# UCD3138_Digital_Controller.net
KiCad netlist of a schematic drawn in Altium Designer
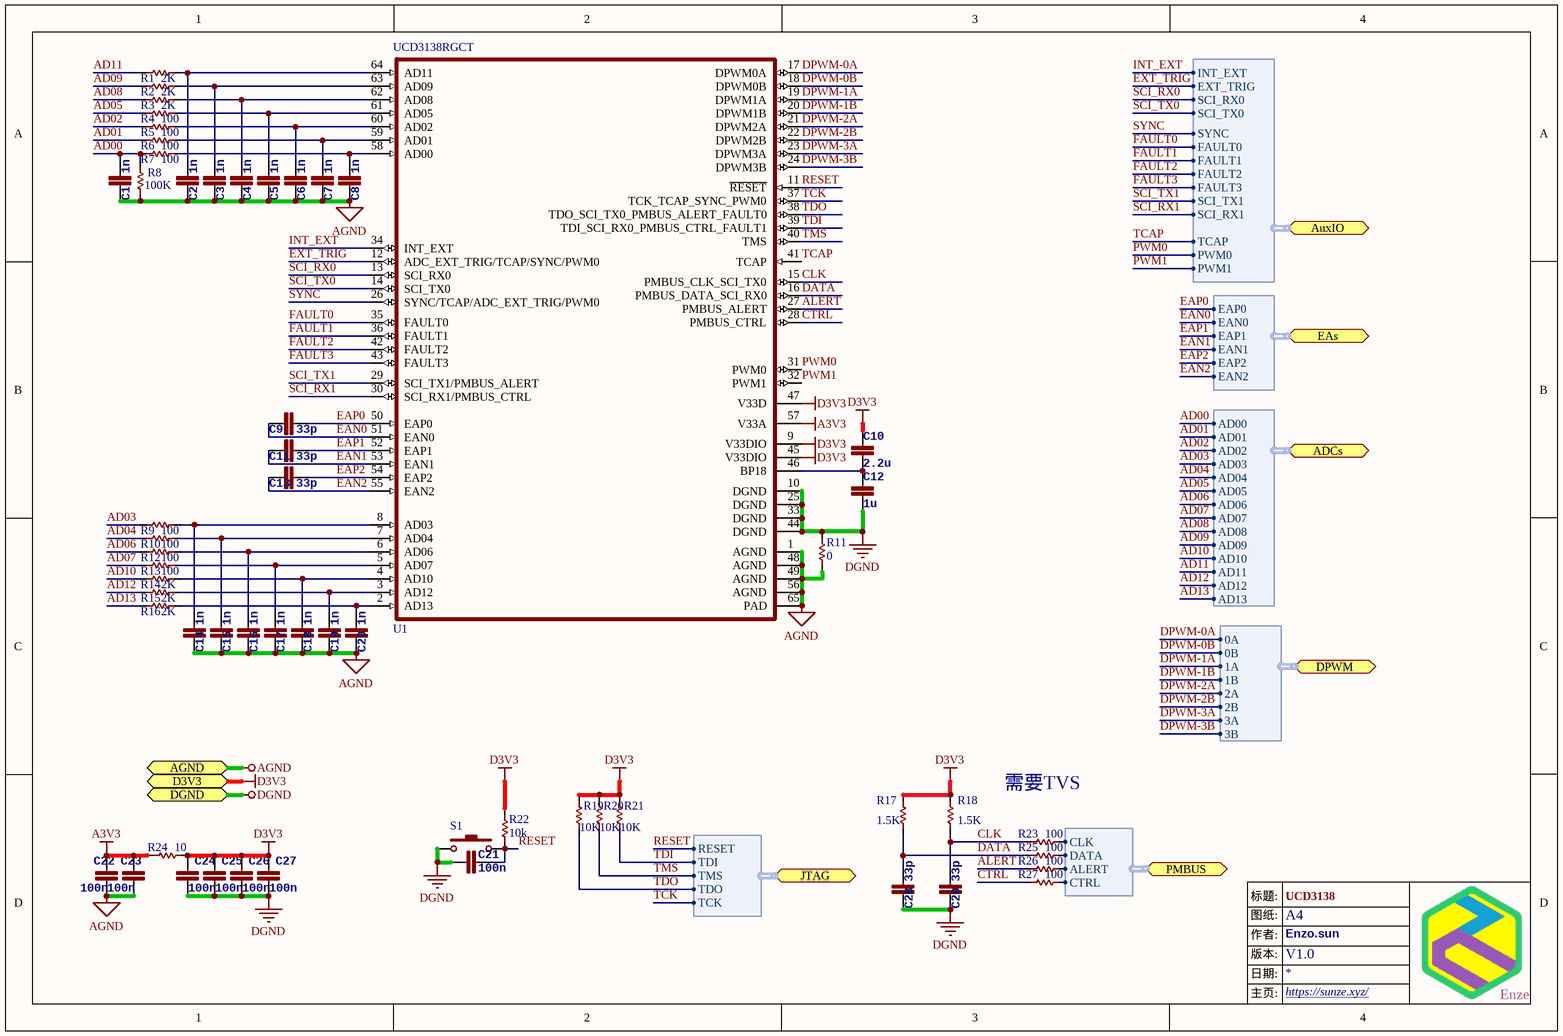
[diagram p0: UCD3138 Digital Controller.SchDoc]

(export (version "E")
  (design (tool "Eeschema 10.0.6"))
  (components
    (comp (ref "C1")
      (value "1n")
      (footprint "0603-R/C-YG")
      (description "<B>CAPACITOR</B>, European symbol")
      (libsource (lib "My_Lib") (part "Capacitor-M"))
    )
    (comp (ref "C2")
      (value "1n")
      (footprint "0603-R/C-YG")
      (description "<B>CAPACITOR</B>, European symbol")
      (libsource (lib "My_Lib") (part "Capacitor-M"))
    )
    (comp (ref "C3")
      (value "1n")
      (footprint "0603-R/C-YG")
      (description "<B>CAPACITOR</B>, European symbol")
      (libsource (lib "My_Lib") (part "Capacitor-M"))
    )
    (comp (ref "C4")
      (value "1n")
      (footprint "0603-R/C-YG")
      (description "<B>CAPACITOR</B>, European symbol")
      (libsource (lib "My_Lib") (part "Capacitor-M"))
    )
    (comp (ref "C5")
      (value "1n")
      (footprint "0603-R/C-YG")
      (description "<B>CAPACITOR</B>, European symbol")
      (libsource (lib "My_Lib") (part "Capacitor-M"))
    )
    (comp (ref "C6")
      (value "1n")
      (footprint "0603-R/C-YG")
      (description "<B>CAPACITOR</B>, European symbol")
      (libsource (lib "My_Lib") (part "Capacitor-M"))
    )
    (comp (ref "C7")
      (value "1n")
      (footprint "0603-R/C-YG")
      (description "<B>CAPACITOR</B>, European symbol")
      (libsource (lib "My_Lib") (part "Capacitor-M"))
    )
    (comp (ref "C8")
      (value "1n")
      (footprint "0603-R/C-YG")
      (description "<B>CAPACITOR</B>, European symbol")
      (libsource (lib "My_Lib") (part "Capacitor-M"))
    )
    (comp (ref "C9")
      (value "33p")
      (footprint "0603-R/C-YG")
      (description "<B>CAPACITOR</B>, European symbol")
      (libsource (lib "") (part "Capacitor-M_1"))
    )
    (comp (ref "C10")
      (value "2.2u")
      (footprint "0603-R/C-YG")
      (description "<B>CAPACITOR</B>, European symbol")
      (libsource (lib "My_Lib") (part "Capacitor-M"))
    )
    (comp (ref "C11")
      (value "33p")
      (footprint "0603-R/C-YG")
      (description "<B>CAPACITOR</B>, European symbol")
      (libsource (lib "") (part "Capacitor-M_1"))
    )
    (comp (ref "C12")
      (value "1u")
      (footprint "0603-R/C-YG")
      (description "<B>CAPACITOR</B>, European symbol")
      (libsource (lib "My_Lib") (part "Capacitor-M"))
    )
    (comp (ref "C13")
      (value "33p")
      (footprint "0603-R/C-YG")
      (description "<B>CAPACITOR</B>, European symbol")
      (libsource (lib "") (part "Capacitor-M_1"))
    )
    (comp (ref "C14")
      (value "1n")
      (footprint "0603-R/C-YG")
      (description "<B>CAPACITOR</B>, European symbol")
      (libsource (lib "My_Lib") (part "Capacitor-M"))
    )
    (comp (ref "C15")
      (value "1n")
      (footprint "0603-R/C-YG")
      (description "<B>CAPACITOR</B>, European symbol")
      (libsource (lib "My_Lib") (part "Capacitor-M"))
    )
    (comp (ref "C16")
      (value "1n")
      (footprint "0603-R/C-YG")
      (description "<B>CAPACITOR</B>, European symbol")
      (libsource (lib "My_Lib") (part "Capacitor-M"))
    )
    (comp (ref "C17")
      (value "1n")
      (footprint "0603-R/C-YG")
      (description "<B>CAPACITOR</B>, European symbol")
      (libsource (lib "My_Lib") (part "Capacitor-M"))
    )
    (comp (ref "C18")
      (value "1n")
      (footprint "0603-R/C-YG")
      (description "<B>CAPACITOR</B>, European symbol")
      (libsource (lib "My_Lib") (part "Capacitor-M"))
    )
    (comp (ref "C19")
      (value "1n")
      (footprint "0603-R/C-YG")
      (description "<B>CAPACITOR</B>, European symbol")
      (libsource (lib "My_Lib") (part "Capacitor-M"))
    )
    (comp (ref "C20")
      (value "1n")
      (footprint "0603-R/C-YG")
      (description "<B>CAPACITOR</B>, European symbol")
      (libsource (lib "My_Lib") (part "Capacitor-M"))
    )
    (comp (ref "C21")
      (value "100n")
      (footprint "0603-R/C-YG")
      (description "<B>CAPACITOR</B>, European symbol")
      (libsource (lib "") (part "Capacitor-M_1"))
    )
    (comp (ref "C22")
      (value "100n")
      (footprint "0603-R/C-YG")
      (description "<B>CAPACITOR</B>, European symbol")
      (libsource (lib "My_Lib") (part "Capacitor-M"))
    )
    (comp (ref "C23")
      (value "100n")
      (footprint "0603-R/C-YG")
      (description "<B>CAPACITOR</B>, European symbol")
      (libsource (lib "My_Lib") (part "Capacitor-M"))
    )
    (comp (ref "C24")
      (value "100n")
      (footprint "0603-R/C-YG")
      (description "<B>CAPACITOR</B>, European symbol")
      (libsource (lib "My_Lib") (part "Capacitor-M"))
    )
    (comp (ref "C25")
      (value "100n")
      (footprint "0603-R/C-YG")
      (description "<B>CAPACITOR</B>, European symbol")
      (libsource (lib "My_Lib") (part "Capacitor-M"))
    )
    (comp (ref "C26")
      (value "100n")
      (footprint "0603-R/C-YG")
      (description "<B>CAPACITOR</B>, European symbol")
      (libsource (lib "My_Lib") (part "Capacitor-M"))
    )
    (comp (ref "C27")
      (value "100n")
      (footprint "0603-R/C-YG")
      (description "<B>CAPACITOR</B>, European symbol")
      (libsource (lib "My_Lib") (part "Capacitor-M"))
    )
    (comp (ref "C28")
      (value "33p")
      (footprint "0603-R/C-YG")
      (description "<B>CAPACITOR</B>, European symbol")
      (libsource (lib "My_Lib") (part "Capacitor-M"))
    )
    (comp (ref "C29")
      (value "33p")
      (footprint "0603-R/C-YG")
      (description "<B>CAPACITOR</B>, European symbol")
      (libsource (lib "My_Lib") (part "Capacitor-M"))
    )
    (comp (ref "R1")
      (value "2K")
      (footprint "0603-R-B")
      (description "电阻")
      (fields (field (name "PUBLISHER") "Altium Limited"))
      (libsource (lib "My_Lib") (part "Resistor-E"))
    )
    (comp (ref "R2")
      (value "2K")
      (footprint "0603-R-B")
      (description "电阻")
      (fields (field (name "PUBLISHER") "Altium Limited"))
      (libsource (lib "My_Lib") (part "Resistor-E"))
    )
    (comp (ref "R3")
      (value "2K")
      (footprint "0603-R-B")
      (description "电阻")
      (fields (field (name "PUBLISHER") "Altium Limited"))
      (libsource (lib "My_Lib") (part "Resistor-E"))
    )
    (comp (ref "R4")
      (value "100")
      (footprint "0603-R-B")
      (description "电阻")
      (fields (field (name "PUBLISHER") "Altium Limited"))
      (libsource (lib "My_Lib") (part "Resistor-E"))
    )
    (comp (ref "R5")
      (value "100")
      (footprint "0603-R-B")
      (description "电阻")
      (fields (field (name "PUBLISHER") "Altium Limited"))
      (libsource (lib "My_Lib") (part "Resistor-E"))
    )
    (comp (ref "R6")
      (value "100")
      (footprint "0603-R-B")
      (description "电阻")
      (fields (field (name "PUBLISHER") "Altium Limited"))
      (libsource (lib "My_Lib") (part "Resistor-E"))
    )
    (comp (ref "R7")
      (value "100")
      (footprint "0603-R-B")
      (description "电阻")
      (fields (field (name "PUBLISHER") "Altium Limited"))
      (libsource (lib "My_Lib") (part "Resistor-E"))
    )
    (comp (ref "R8")
      (value "100K")
      (footprint "0603-R-B")
      (description "电阻")
      (fields (field (name "PUBLISHER") "Altium Limited"))
      (libsource (lib "My_Lib") (part "Resistor-E"))
    )
    (comp (ref "R9")
      (value "100")
      (footprint "0603-R-B")
      (description "电阻")
      (fields (field (name "PUBLISHER") "Altium Limited"))
      (libsource (lib "My_Lib") (part "Resistor-E"))
    )
    (comp (ref "R10")
      (value "100")
      (footprint "0603-R-B")
      (description "电阻")
      (fields (field (name "PUBLISHER") "Altium Limited"))
      (libsource (lib "My_Lib") (part "Resistor-E"))
    )
    (comp (ref "R11")
      (value "0")
      (footprint "0805R")
      (description "电阻")
      (fields (field (name "PUBLISHER") "Altium Limited"))
      (libsource (lib "My_Lib") (part "Resistor-E"))
    )
    (comp (ref "R12")
      (value "100")
      (footprint "0603-R-B")
      (description "电阻")
      (fields (field (name "PUBLISHER") "Altium Limited"))
      (libsource (lib "My_Lib") (part "Resistor-E"))
    )
    (comp (ref "R13")
      (value "100")
      (footprint "0603-R-B")
      (description "电阻")
      (fields (field (name "PUBLISHER") "Altium Limited"))
      (libsource (lib "My_Lib") (part "Resistor-E"))
    )
    (comp (ref "R14")
      (value "2K")
      (footprint "0603-R-B")
      (description "电阻")
      (fields (field (name "PUBLISHER") "Altium Limited"))
      (libsource (lib "My_Lib") (part "Resistor-E"))
    )
    (comp (ref "R15")
      (value "2K")
      (footprint "0603-R-B")
      (description "电阻")
      (fields (field (name "PUBLISHER") "Altium Limited"))
      (libsource (lib "My_Lib") (part "Resistor-E"))
    )
    (comp (ref "R16")
      (value "2K")
      (footprint "0603-R-B")
      (description "电阻")
      (fields (field (name "PUBLISHER") "Altium Limited"))
      (libsource (lib "My_Lib") (part "Resistor-E"))
    )
    (comp (ref "R17")
      (value "1.5K")
      (footprint "0603-R-B")
      (description "电阻")
      (fields (field (name "PUBLISHER") "Altium Limited"))
      (libsource (lib "My_Lib") (part "Resistor-E"))
    )
    (comp (ref "R18")
      (value "1.5K")
      (footprint "0603-R-B")
      (description "电阻")
      (fields (field (name "PUBLISHER") "Altium Limited"))
      (libsource (lib "My_Lib") (part "Resistor-E"))
    )
    (comp (ref "R19")
      (value "10K")
      (footprint "0603-R-B")
      (description "电阻")
      (fields (field (name "PUBLISHER") "Altium Limited"))
      (libsource (lib "My_Lib") (part "Resistor-E"))
    )
    (comp (ref "R20")
      (value "10K")
      (footprint "0603-R-B")
      (description "电阻")
      (fields (field (name "PUBLISHER") "Altium Limited"))
      (libsource (lib "My_Lib") (part "Resistor-E"))
    )
    (comp (ref "R21")
      (value "10K")
      (footprint "0603-R-B")
      (description "电阻")
      (fields (field (name "PUBLISHER") "Altium Limited"))
      (libsource (lib "My_Lib") (part "Resistor-E"))
    )
    (comp (ref "R22")
      (value "10k")
      (footprint "0603-R-B")
      (description "电阻")
      (fields (field (name "PUBLISHER") "Altium Limited"))
      (libsource (lib "My_Lib") (part "Resistor-E"))
    )
    (comp (ref "R23")
      (value "100")
      (footprint "0603-R-B")
      (description "电阻")
      (fields (field (name "PUBLISHER") "Altium Limited"))
      (libsource (lib "My_Lib") (part "Resistor-E"))
    )
    (comp (ref "R24")
      (value "10")
      (footprint "0805R")
      (description "电阻")
      (fields (field (name "PUBLISHER") "Altium Limited"))
      (libsource (lib "My_Lib") (part "Resistor-E"))
    )
    (comp (ref "R25")
      (value "100")
      (footprint "0603-R-B")
      (description "电阻")
      (fields (field (name "PUBLISHER") "Altium Limited"))
      (libsource (lib "My_Lib") (part "Resistor-E"))
    )
    (comp (ref "R26")
      (value "100")
      (footprint "0603-R-B")
      (description "电阻")
      (fields (field (name "PUBLISHER") "Altium Limited"))
      (libsource (lib "My_Lib") (part "Resistor-E"))
    )
    (comp (ref "R27")
      (value "100")
      (footprint "0603-R-B")
      (description "电阻")
      (fields (field (name "PUBLISHER") "Altium Limited"))
      (libsource (lib "My_Lib") (part "Resistor-E"))
    )
    (comp (ref "S1")
      (value "SW-PB")
      (footprint "SW-SMD1")
      (description "Switch")
      (fields (field (name "PUBLISHER") "Altium Limited"))
      (libsource (lib "My_Lib") (part "SW-PB"))
    )
    (comp (ref "UCD3138RGCT")
      (value "U1")
      (footprint "VQFN-64")
      (description "64Pins")
      (libsource (lib "My_Lib") (part "UCD3138RGCT"))
    )
  )
  (nets
    (net (code "7") (name "/AD00") (class "Default")
      (node (ref "C1") (pin "2") (pinfunction "2_2") (pintype "passive"))
      (node (ref "R7") (pin "2") (pinfunction "2_2") (pintype "passive"))
      (node (ref "R8") (pin "1") (pinfunction "1_1") (pintype "passive"))
    )
    (net (code "8") (name "/AD01") (class "Default")
      (node (ref "R6") (pin "2") (pinfunction "2_2") (pintype "passive"))
    )
    (net (code "9") (name "/AD02") (class "Default")
      (node (ref "R5") (pin "2") (pinfunction "2_2") (pintype "passive"))
    )
    (net (code "10") (name "/AD03") (class "Default")
      (node (ref "R9") (pin "2") (pinfunction "2_2") (pintype "passive"))
    )
    (net (code "11") (name "/AD04") (class "Default")
      (node (ref "R10") (pin "2") (pinfunction "2_2") (pintype "passive"))
    )
    (net (code "12") (name "/AD05") (class "Default")
      (node (ref "R4") (pin "2") (pinfunction "2_2") (pintype "passive"))
    )
    (net (code "13") (name "/AD06") (class "Default")
      (node (ref "R12") (pin "2") (pinfunction "2_2") (pintype "passive"))
    )
    (net (code "14") (name "/AD07") (class "Default")
      (node (ref "R13") (pin "2") (pinfunction "2_2") (pintype "passive"))
    )
    (net (code "15") (name "/AD08") (class "Default")
      (node (ref "R3") (pin "2") (pinfunction "2_2") (pintype "passive"))
    )
    (net (code "16") (name "/AD09") (class "Default")
      (node (ref "R2") (pin "2") (pinfunction "2_2") (pintype "passive"))
    )
    (net (code "17") (name "/AD10") (class "Default")
      (node (ref "R14") (pin "2") (pinfunction "2_2") (pintype "passive"))
    )
    (net (code "18") (name "/AD11") (class "Default")
      (node (ref "R1") (pin "2") (pinfunction "2_2") (pintype "passive"))
    )
    (net (code "19") (name "/AD12") (class "Default")
      (node (ref "R15") (pin "2") (pinfunction "2_2") (pintype "passive"))
    )
    (net (code "20") (name "/AD13") (class "Default")
      (node (ref "R16") (pin "2") (pinfunction "2_2") (pintype "passive"))
    )
    (net (code "21") (name "/ALERT") (class "Default")
      (node (ref "R26") (pin "2") (pinfunction "2_2") (pintype "passive"))
      (node (ref "UCD3138RGCT") (pin "27") (pinfunction "PMBUS_ALERT_27") (pintype "bidirectional"))
    )
    (net (code "22") (name "/CLK") (class "Default")
      (node (ref "C29") (pin "2") (pinfunction "2_2") (pintype "passive"))
      (node (ref "R18") (pin "1") (pinfunction "1_1") (pintype "passive"))
      (node (ref "R23") (pin "2") (pinfunction "2_2") (pintype "passive"))
      (node (ref "UCD3138RGCT") (pin "15") (pinfunction "PMBUS_CLK_SCI_TX0_15") (pintype "bidirectional"))
    )
    (net (code "23") (name "/CTRL") (class "Default")
      (node (ref "R27") (pin "2") (pinfunction "2_2") (pintype "passive"))
      (node (ref "UCD3138RGCT") (pin "28") (pinfunction "PMBUS_CTRL_28") (pintype "bidirectional"))
    )
    (net (code "24") (name "/DATA") (class "Default")
      (node (ref "C28") (pin "2") (pinfunction "2_2") (pintype "passive"))
      (node (ref "R17") (pin "1") (pinfunction "1_1") (pintype "passive"))
      (node (ref "R25") (pin "2") (pinfunction "2_2") (pintype "passive"))
      (node (ref "UCD3138RGCT") (pin "16") (pinfunction "PMBUS_DATA_SCI_RX0_16") (pintype "bidirectional"))
    )
    (net (code "25") (name "/DPWM-0A") (class "Default")
      (node (ref "UCD3138RGCT") (pin "17") (pinfunction "DPWM0A_17") (pintype "bidirectional"))
    )
    (net (code "26") (name "/DPWM-0B") (class "Default")
      (node (ref "UCD3138RGCT") (pin "18") (pinfunction "DPWM0B_18") (pintype "bidirectional"))
    )
    (net (code "27") (name "/DPWM-1A") (class "Default")
      (node (ref "UCD3138RGCT") (pin "19") (pinfunction "DPWM1A_19") (pintype "bidirectional"))
    )
    (net (code "28") (name "/DPWM-1B") (class "Default")
      (node (ref "UCD3138RGCT") (pin "20") (pinfunction "DPWM1B_20") (pintype "bidirectional"))
    )
    (net (code "29") (name "/DPWM-2A") (class "Default")
      (node (ref "UCD3138RGCT") (pin "21") (pinfunction "DPWM2A_21") (pintype "bidirectional"))
    )
    (net (code "30") (name "/DPWM-2B") (class "Default")
      (node (ref "UCD3138RGCT") (pin "22") (pinfunction "DPWM2B_22") (pintype "bidirectional"))
    )
    (net (code "31") (name "/DPWM-3A") (class "Default")
      (node (ref "UCD3138RGCT") (pin "23") (pinfunction "DPWM3A_23") (pintype "bidirectional"))
    )
    (net (code "32") (name "/DPWM-3B") (class "Default")
      (node (ref "UCD3138RGCT") (pin "24") (pinfunction "DPWM3B_24") (pintype "bidirectional"))
    )
    (net (code "33") (name "/EAN0") (class "Default")
      (node (ref "C9") (pin "1") (pinfunction "1_1") (pintype "passive"))
      (node (ref "UCD3138RGCT") (pin "51") (pinfunction "EAN0_51") (pintype "input"))
    )
    (net (code "34") (name "/EAN1") (class "Default")
      (node (ref "C11") (pin "1") (pinfunction "1_1") (pintype "passive"))
      (node (ref "UCD3138RGCT") (pin "53") (pinfunction "EAN1_53") (pintype "input"))
    )
    (net (code "35") (name "/EAN2") (class "Default")
      (node (ref "C13") (pin "1") (pinfunction "1_1") (pintype "passive"))
      (node (ref "UCD3138RGCT") (pin "55") (pinfunction "EAN2_55") (pintype "input"))
    )
    (net (code "36") (name "/EAP0") (class "Default")
      (node (ref "C9") (pin "2") (pinfunction "2_2") (pintype "passive"))
      (node (ref "UCD3138RGCT") (pin "50") (pinfunction "EAP0_50") (pintype "input"))
    )
    (net (code "37") (name "/EAP1") (class "Default")
      (node (ref "C11") (pin "2") (pinfunction "2_2") (pintype "passive"))
      (node (ref "UCD3138RGCT") (pin "52") (pinfunction "EAP1_52") (pintype "input"))
    )
    (net (code "38") (name "/EAP2") (class "Default")
      (node (ref "C13") (pin "2") (pinfunction "2_2") (pintype "passive"))
      (node (ref "UCD3138RGCT") (pin "54") (pinfunction "EAP2_54") (pintype "input"))
    )
    (net (code "39") (name "/EXT_TRIG") (class "Default")
      (node (ref "UCD3138RGCT") (pin "12") (pinfunction "ADC_EXT_TRIG/TCAP/SYNC/PWM0_12") (pintype "bidirectional"))
    )
    (net (code "40") (name "/FAULT0") (class "Default")
      (node (ref "UCD3138RGCT") (pin "35") (pinfunction "FAULT0_35") (pintype "bidirectional"))
    )
    (net (code "41") (name "/FAULT1") (class "Default")
      (node (ref "UCD3138RGCT") (pin "36") (pinfunction "FAULT1_36") (pintype "bidirectional"))
    )
    (net (code "42") (name "/FAULT2") (class "Default")
      (node (ref "UCD3138RGCT") (pin "42") (pinfunction "FAULT2_42") (pintype "bidirectional"))
    )
    (net (code "43") (name "/FAULT3") (class "Default")
      (node (ref "UCD3138RGCT") (pin "43") (pinfunction "FAULT3_43") (pintype "bidirectional"))
    )
    (net (code "44") (name "/INT_EXT") (class "Default")
      (node (ref "UCD3138RGCT") (pin "34") (pinfunction "INT_EXT_34") (pintype "bidirectional"))
    )
    (net (code "45") (name "/PWM0") (class "Default")
      (node (ref "UCD3138RGCT") (pin "31") (pinfunction "PWM0_31") (pintype "bidirectional"))
    )
    (net (code "46") (name "/PWM1") (class "Default")
      (node (ref "UCD3138RGCT") (pin "32") (pinfunction "PWM1_32") (pintype "bidirectional"))
    )
    (net (code "47") (name "/RESET") (class "Default")
      (node (ref "C21") (pin "2") (pinfunction "2_2") (pintype "passive"))
      (node (ref "R22") (pin "1") (pinfunction "1_1") (pintype "passive"))
      (node (ref "S1") (pin "2") (pinfunction "2_2") (pintype "passive"))
      (node (ref "UCD3138RGCT") (pin "11") (pinfunction "~{RESET}_11") (pintype "input"))
    )
    (net (code "48") (name "/SCI_RX0") (class "Default")
      (node (ref "UCD3138RGCT") (pin "13") (pinfunction "SCI_RX0_13") (pintype "bidirectional"))
    )
    (net (code "49") (name "/SCI_RX1") (class "Default")
      (node (ref "UCD3138RGCT") (pin "30") (pinfunction "SCI_RX1/PMBUS_CTRL_30") (pintype "bidirectional"))
    )
    (net (code "50") (name "/SCI_TX0") (class "Default")
      (node (ref "UCD3138RGCT") (pin "14") (pinfunction "SCI_TX0_14") (pintype "bidirectional"))
    )
    (net (code "51") (name "/SCI_TX1") (class "Default")
      (node (ref "UCD3138RGCT") (pin "29") (pinfunction "SCI_TX1/PMBUS_ALERT_29") (pintype "bidirectional"))
    )
    (net (code "52") (name "/SYNC") (class "Default")
      (node (ref "UCD3138RGCT") (pin "26") (pinfunction "SYNC/TCAP/ADC_EXT_TRIG/PWM0_26") (pintype "bidirectional"))
    )
    (net (code "53") (name "/TCAP") (class "Default")
      (node (ref "UCD3138RGCT") (pin "41") (pinfunction "TCAP_41") (pintype "input"))
    )
    (net (code "54") (name "/TCK") (class "Default")
      (node (ref "UCD3138RGCT") (pin "37") (pinfunction "TCK_TCAP_SYNC_PWM0_37") (pintype "bidirectional"))
    )
    (net (code "55") (name "/TDI") (class "Default")
      (node (ref "R21") (pin "1") (pinfunction "1_1") (pintype "passive"))
      (node (ref "UCD3138RGCT") (pin "39") (pinfunction "TDI_SCI_RX0_PMBUS_CTRL_FAULT1_39") (pintype "bidirectional"))
    )
    (net (code "56") (name "/TDO") (class "Default")
      (node (ref "R19") (pin "1") (pinfunction "1_1") (pintype "passive"))
      (node (ref "UCD3138RGCT") (pin "38") (pinfunction "TDO_SCI_TX0_PMBUS_ALERT_FAULT0_38") (pintype "bidirectional"))
    )
    (net (code "57") (name "/TMS") (class "Default")
      (node (ref "R20") (pin "1") (pinfunction "1_1") (pintype "passive"))
      (node (ref "UCD3138RGCT") (pin "40") (pinfunction "TMS_40") (pintype "bidirectional"))
    )
    (net (code "64") (name "A3V3") (class "Default")
      (node (ref "C22") (pin "2") (pinfunction "2_2") (pintype "passive"))
      (node (ref "C23") (pin "2") (pinfunction "2_2") (pintype "passive"))
      (node (ref "R24") (pin "2") (pinfunction "2_2") (pintype "passive"))
      (node (ref "UCD3138RGCT") (pin "57") (pinfunction "V33A_57") (pintype "power_in"))
    )
    (net (code "65") (name "AGND") (class "Default")
      (node (ref "C1") (pin "1") (pinfunction "1_1") (pintype "passive"))
      (node (ref "C14") (pin "1") (pinfunction "1_1") (pintype "passive"))
      (node (ref "C15") (pin "1") (pinfunction "1_1") (pintype "passive"))
      (node (ref "C16") (pin "1") (pinfunction "1_1") (pintype "passive"))
      (node (ref "C17") (pin "1") (pinfunction "1_1") (pintype "passive"))
      (node (ref "C18") (pin "1") (pinfunction "1_1") (pintype "passive"))
      (node (ref "C19") (pin "1") (pinfunction "1_1") (pintype "passive"))
      (node (ref "C2") (pin "1") (pinfunction "1_1") (pintype "passive"))
      (node (ref "C20") (pin "1") (pinfunction "1_1") (pintype "passive"))
      (node (ref "C22") (pin "1") (pinfunction "1_1") (pintype "passive"))
      (node (ref "C23") (pin "1") (pinfunction "1_1") (pintype "passive"))
      (node (ref "C3") (pin "1") (pinfunction "1_1") (pintype "passive"))
      (node (ref "C4") (pin "1") (pinfunction "1_1") (pintype "passive"))
      (node (ref "C5") (pin "1") (pinfunction "1_1") (pintype "passive"))
      (node (ref "C6") (pin "1") (pinfunction "1_1") (pintype "passive"))
      (node (ref "C7") (pin "1") (pinfunction "1_1") (pintype "passive"))
      (node (ref "C8") (pin "1") (pinfunction "1_1") (pintype "passive"))
      (node (ref "R11") (pin "2") (pinfunction "2_2") (pintype "passive"))
      (node (ref "R8") (pin "2") (pinfunction "2_2") (pintype "passive"))
      (node (ref "UCD3138RGCT") (pin "1") (pinfunction "AGND_1") (pintype "power_in"))
      (node (ref "UCD3138RGCT") (pin "48") (pinfunction "AGND_48") (pintype "power_in"))
      (node (ref "UCD3138RGCT") (pin "49") (pinfunction "AGND_49") (pintype "power_in"))
      (node (ref "UCD3138RGCT") (pin "56") (pinfunction "AGND_56") (pintype "power_in"))
      (node (ref "UCD3138RGCT") (pin "65") (pinfunction "PAD_65") (pintype "power_in"))
    )
    (net (code "66") (name "D3V3") (class "Default")
      (node (ref "C10") (pin "2") (pinfunction "2_2") (pintype "passive"))
      (node (ref "C24") (pin "2") (pinfunction "2_2") (pintype "passive"))
      (node (ref "C25") (pin "2") (pinfunction "2_2") (pintype "passive"))
      (node (ref "C26") (pin "2") (pinfunction "2_2") (pintype "passive"))
      (node (ref "C27") (pin "2") (pinfunction "2_2") (pintype "passive"))
      (node (ref "R17") (pin "2") (pinfunction "2_2") (pintype "passive"))
      (node (ref "R18") (pin "2") (pinfunction "2_2") (pintype "passive"))
      (node (ref "R19") (pin "2") (pinfunction "2_2") (pintype "passive"))
      (node (ref "R20") (pin "2") (pinfunction "2_2") (pintype "passive"))
      (node (ref "R21") (pin "2") (pinfunction "2_2") (pintype "passive"))
      (node (ref "R22") (pin "2") (pinfunction "2_2") (pintype "passive"))
      (node (ref "R24") (pin "1") (pinfunction "1_1") (pintype "passive"))
      (node (ref "UCD3138RGCT") (pin "45") (pinfunction "V33DIO_45") (pintype "power_in"))
      (node (ref "UCD3138RGCT") (pin "47") (pinfunction "V33D_47") (pintype "power_in"))
      (node (ref "UCD3138RGCT") (pin "9") (pinfunction "V33DIO_9") (pintype "power_in"))
    )
    (net (code "67") (name "DGND") (class "Default")
      (node (ref "C12") (pin "1") (pinfunction "1_1") (pintype "passive"))
      (node (ref "C21") (pin "1") (pinfunction "1_1") (pintype "passive"))
      (node (ref "C24") (pin "1") (pinfunction "1_1") (pintype "passive"))
      (node (ref "C25") (pin "1") (pinfunction "1_1") (pintype "passive"))
      (node (ref "C26") (pin "1") (pinfunction "1_1") (pintype "passive"))
      (node (ref "C27") (pin "1") (pinfunction "1_1") (pintype "passive"))
      (node (ref "C28") (pin "1") (pinfunction "1_1") (pintype "passive"))
      (node (ref "C29") (pin "1") (pinfunction "1_1") (pintype "passive"))
      (node (ref "R11") (pin "1") (pinfunction "1_1") (pintype "passive"))
      (node (ref "S1") (pin "1") (pinfunction "1_1") (pintype "passive"))
      (node (ref "UCD3138RGCT") (pin "10") (pinfunction "DGND_10") (pintype "power_in"))
      (node (ref "UCD3138RGCT") (pin "25") (pinfunction "DGND_25") (pintype "power_in"))
      (node (ref "UCD3138RGCT") (pin "33") (pinfunction "DGND_33") (pintype "power_in"))
      (node (ref "UCD3138RGCT") (pin "44") (pinfunction "DGND_44") (pintype "power_in"))
    )
    (net (code "68") (name "Net-(UCD3138RGCT-AD00)") (class "Default")
      (node (ref "C8") (pin "2") (pinfunction "2_2") (pintype "passive"))
      (node (ref "R7") (pin "1") (pinfunction "1_1") (pintype "passive"))
      (node (ref "UCD3138RGCT") (pin "58") (pinfunction "AD00_58") (pintype "input"))
    )
    (net (code "69") (name "Net-(UCD3138RGCT-AD01)") (class "Default")
      (node (ref "C7") (pin "2") (pinfunction "2_2") (pintype "passive"))
      (node (ref "R6") (pin "1") (pinfunction "1_1") (pintype "passive"))
      (node (ref "UCD3138RGCT") (pin "59") (pinfunction "AD01_59") (pintype "input"))
    )
    (net (code "70") (name "Net-(UCD3138RGCT-AD02)") (class "Default")
      (node (ref "C6") (pin "2") (pinfunction "2_2") (pintype "passive"))
      (node (ref "R5") (pin "1") (pinfunction "1_1") (pintype "passive"))
      (node (ref "UCD3138RGCT") (pin "60") (pinfunction "AD02_60") (pintype "input"))
    )
    (net (code "71") (name "Net-(UCD3138RGCT-AD03)") (class "Default")
      (node (ref "C14") (pin "2") (pinfunction "2_2") (pintype "passive"))
      (node (ref "R9") (pin "1") (pinfunction "1_1") (pintype "passive"))
      (node (ref "UCD3138RGCT") (pin "8") (pinfunction "AD03_8") (pintype "input"))
    )
    (net (code "72") (name "Net-(UCD3138RGCT-AD04)") (class "Default")
      (node (ref "C15") (pin "2") (pinfunction "2_2") (pintype "passive"))
      (node (ref "R10") (pin "1") (pinfunction "1_1") (pintype "passive"))
      (node (ref "UCD3138RGCT") (pin "7") (pinfunction "AD04_7") (pintype "input"))
    )
    (net (code "73") (name "Net-(UCD3138RGCT-AD05)") (class "Default")
      (node (ref "C5") (pin "2") (pinfunction "2_2") (pintype "passive"))
      (node (ref "R4") (pin "1") (pinfunction "1_1") (pintype "passive"))
      (node (ref "UCD3138RGCT") (pin "61") (pinfunction "AD05_61") (pintype "input"))
    )
    (net (code "74") (name "Net-(UCD3138RGCT-AD06)") (class "Default")
      (node (ref "C16") (pin "2") (pinfunction "2_2") (pintype "passive"))
      (node (ref "R12") (pin "1") (pinfunction "1_1") (pintype "passive"))
      (node (ref "UCD3138RGCT") (pin "6") (pinfunction "AD06_6") (pintype "input"))
    )
    (net (code "75") (name "Net-(UCD3138RGCT-AD07)") (class "Default")
      (node (ref "C17") (pin "2") (pinfunction "2_2") (pintype "passive"))
      (node (ref "R13") (pin "1") (pinfunction "1_1") (pintype "passive"))
      (node (ref "UCD3138RGCT") (pin "5") (pinfunction "AD07_5") (pintype "input"))
    )
    (net (code "76") (name "Net-(UCD3138RGCT-AD08)") (class "Default")
      (node (ref "C4") (pin "2") (pinfunction "2_2") (pintype "passive"))
      (node (ref "R3") (pin "1") (pinfunction "1_1") (pintype "passive"))
      (node (ref "UCD3138RGCT") (pin "62") (pinfunction "AD08_62") (pintype "input"))
    )
    (net (code "77") (name "Net-(UCD3138RGCT-AD09)") (class "Default")
      (node (ref "C3") (pin "2") (pinfunction "2_2") (pintype "passive"))
      (node (ref "R2") (pin "1") (pinfunction "1_1") (pintype "passive"))
      (node (ref "UCD3138RGCT") (pin "63") (pinfunction "AD09_63") (pintype "input"))
    )
    (net (code "78") (name "Net-(UCD3138RGCT-AD10)") (class "Default")
      (node (ref "C18") (pin "2") (pinfunction "2_2") (pintype "passive"))
      (node (ref "R14") (pin "1") (pinfunction "1_1") (pintype "passive"))
      (node (ref "UCD3138RGCT") (pin "4") (pinfunction "AD10_4") (pintype "input"))
    )
    (net (code "79") (name "Net-(UCD3138RGCT-AD11)") (class "Default")
      (node (ref "C2") (pin "2") (pinfunction "2_2") (pintype "passive"))
      (node (ref "R1") (pin "1") (pinfunction "1_1") (pintype "passive"))
      (node (ref "UCD3138RGCT") (pin "64") (pinfunction "AD11_64") (pintype "input"))
    )
    (net (code "80") (name "Net-(UCD3138RGCT-AD12)") (class "Default")
      (node (ref "C19") (pin "2") (pinfunction "2_2") (pintype "passive"))
      (node (ref "R15") (pin "1") (pinfunction "1_1") (pintype "passive"))
      (node (ref "UCD3138RGCT") (pin "3") (pinfunction "AD12_3") (pintype "input"))
    )
    (net (code "81") (name "Net-(UCD3138RGCT-AD13)") (class "Default")
      (node (ref "C20") (pin "2") (pinfunction "2_2") (pintype "passive"))
      (node (ref "R16") (pin "1") (pinfunction "1_1") (pintype "passive"))
      (node (ref "UCD3138RGCT") (pin "2") (pinfunction "AD13_2") (pintype "input"))
    )
    (net (code "82") (name "Net-(UCD3138RGCT-BP18)") (class "Default")
      (node (ref "C10") (pin "1") (pinfunction "1_1") (pintype "passive"))
      (node (ref "C12") (pin "2") (pinfunction "2_2") (pintype "passive"))
      (node (ref "UCD3138RGCT") (pin "46") (pinfunction "BP18_46") (pintype "power_in"))
    )
    (net (code "83") (name "unconnected-(R23-Pad1)") (class "Default")
      (node (ref "R23") (pin "1") (pinfunction "1_1") (pintype "passive"))
    )
    (net (code "84") (name "unconnected-(R25-Pad1)") (class "Default")
      (node (ref "R25") (pin "1") (pinfunction "1_1") (pintype "passive"))
    )
    (net (code "85") (name "unconnected-(R26-Pad1)") (class "Default")
      (node (ref "R26") (pin "1") (pinfunction "1_1") (pintype "passive"))
    )
    (net (code "86") (name "unconnected-(R27-Pad1)") (class "Default")
      (node (ref "R27") (pin "1") (pinfunction "1_1") (pintype "passive"))
    )
  )
)
